# StepDrv.net
KiCad netlist of a schematic drawn in EAGLE
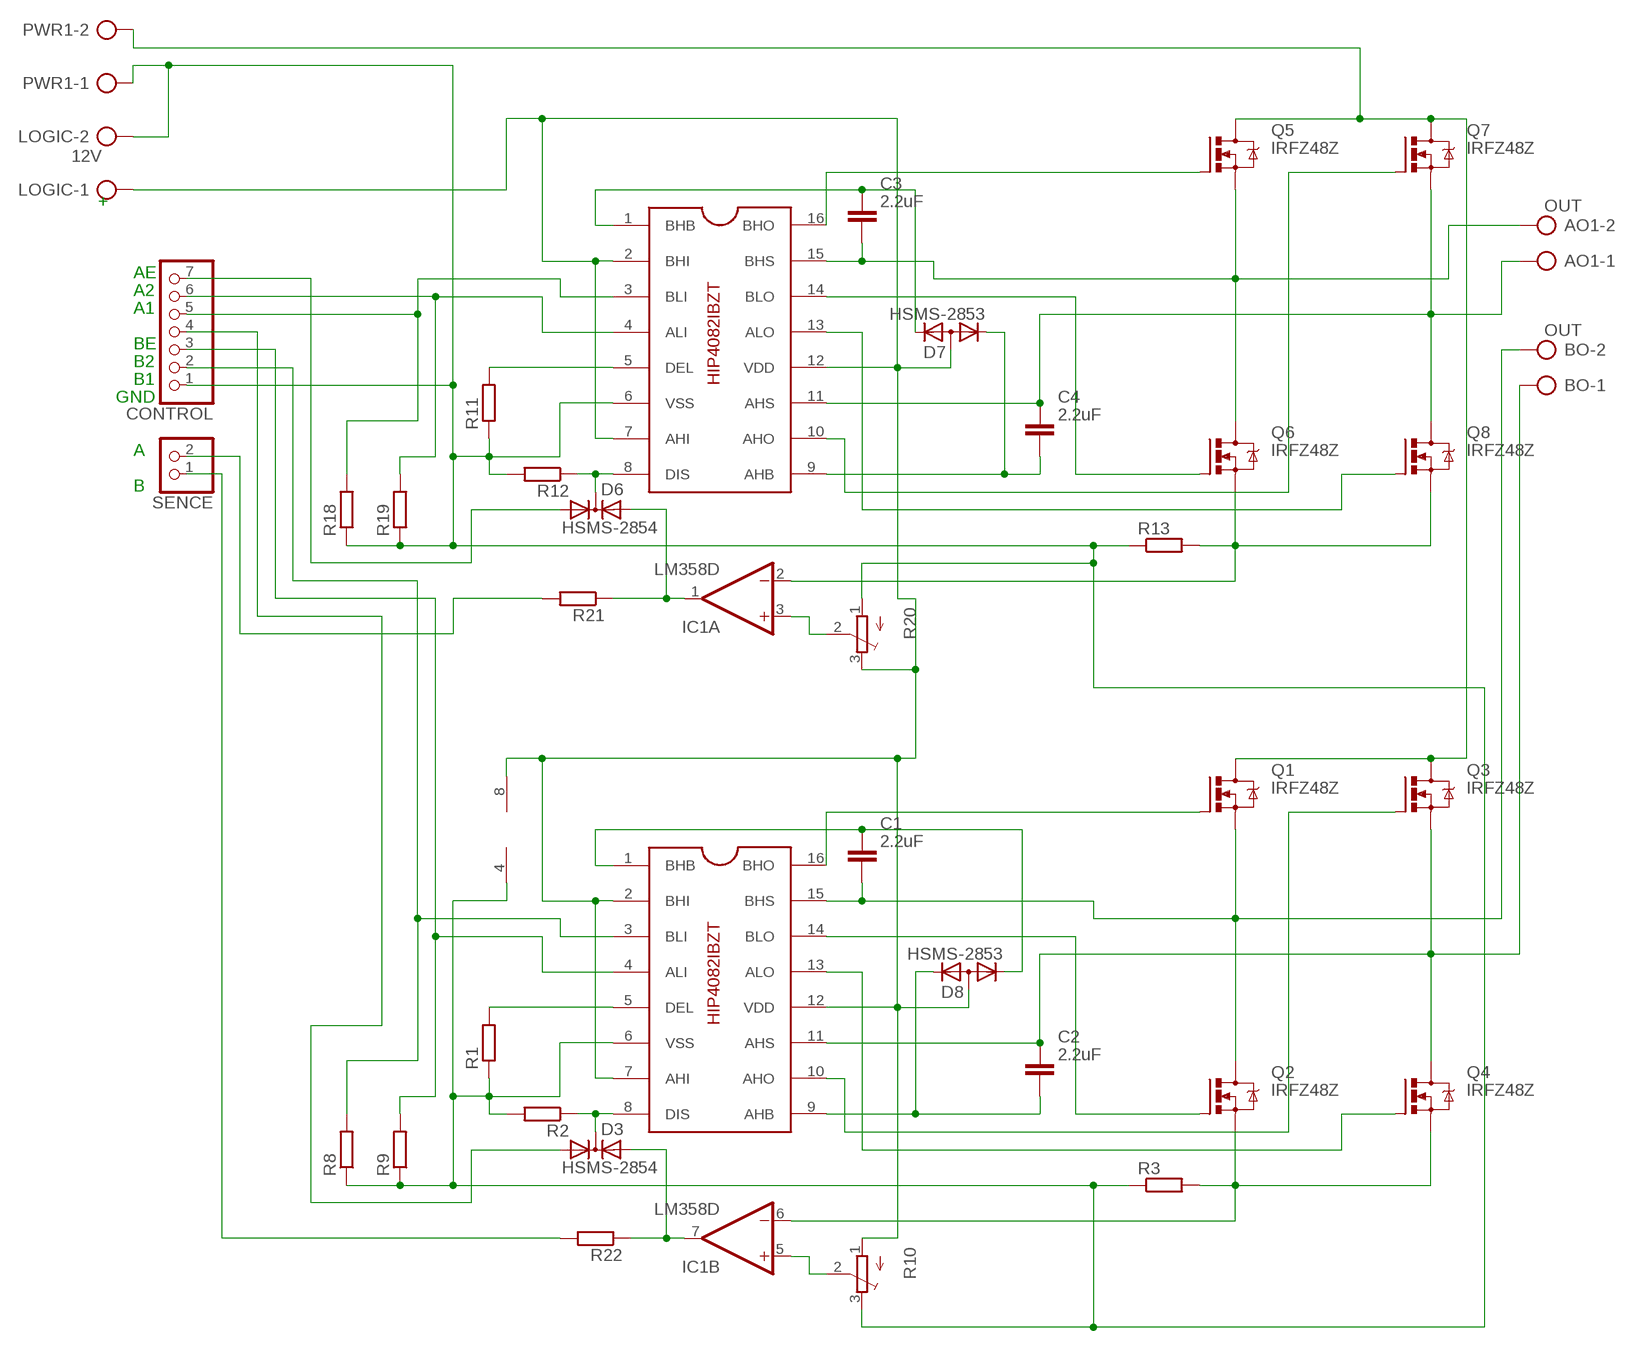
[diagram p0: schematic, sheet 1]

(export (version "E")
  (design (tool "Eeschema 10.0.6"))
  (components
    (comp (ref "AO1")
      (value "OUT")
      (footprint "eagle-import:AK300_2")
      (libsource (lib "eagle-import") (part "AK300/2"))
    )
    (comp (ref "BO")
      (value "OUT")
      (footprint "eagle-import:AK300_2")
      (libsource (lib "eagle-import") (part "AK300/2"))
    )
    (comp (ref "C1")
      (value "2.2uF")
      (footprint "eagle-import:C1206")
      (libsource (lib "eagle-import") (part "CAPACITOR_NPOL-1206"))
    )
    (comp (ref "C2")
      (value "2.2uF")
      (footprint "eagle-import:C1206")
      (libsource (lib "eagle-import") (part "CAPACITOR_NPOL-1206"))
    )
    (comp (ref "C3")
      (value "2.2uF")
      (footprint "eagle-import:C1206")
      (libsource (lib "eagle-import") (part "CAPACITOR_NPOL-1206"))
    )
    (comp (ref "C4")
      (value "2.2uF")
      (footprint "eagle-import:C1206")
      (libsource (lib "eagle-import") (part "CAPACITOR_NPOL-1206"))
    )
    (comp (ref "CONTROL")
      (value "PINHD-1X7")
      (footprint "eagle-import:1X07")
      (libsource (lib "eagle-import") (part "PINHD-1X7"))
    )
    (comp (ref "D3")
      (value "HSMS-2854")
      (footprint "eagle-import:SOT23")
      (libsource (lib "eagle-import") (part "HSMS-2854"))
    )
    (comp (ref "D6")
      (value "HSMS-2854")
      (footprint "eagle-import:SOT23")
      (libsource (lib "eagle-import") (part "HSMS-2854"))
    )
    (comp (ref "D7")
      (value "HSMS-2853")
      (footprint "eagle-import:SOT23")
      (libsource (lib "eagle-import") (part "HSMS-2853"))
    )
    (comp (ref "D8")
      (value "HSMS-2853")
      (footprint "eagle-import:SOT23")
      (libsource (lib "eagle-import") (part "HSMS-2853"))
    )
    (comp (ref "IC1")
      (value "LM358D")
      (footprint "eagle-import:SO08")
      (libsource (lib "eagle-import") (part "LM358D"))
    )
    (comp (ref "LOGIC")
      (value "12V")
      (footprint "eagle-import:AK300_2")
      (libsource (lib "eagle-import") (part "AK300/2"))
    )
    (comp (ref "PWR1")
      (value "AK300/2")
      (footprint "eagle-import:AK300_2")
      (libsource (lib "eagle-import") (part "AK300/2"))
    )
    (comp (ref "Q1")
      (value "IRFZ48Z")
      (footprint "eagle-import:TO220BH")
      (libsource (lib "eagle-import") (part "IRFZ48Z"))
    )
    (comp (ref "Q2")
      (value "IRFZ48Z")
      (footprint "eagle-import:TO220BH")
      (libsource (lib "eagle-import") (part "IRFZ48Z"))
    )
    (comp (ref "Q3")
      (value "IRFZ48Z")
      (footprint "eagle-import:TO220BH")
      (libsource (lib "eagle-import") (part "IRFZ48Z"))
    )
    (comp (ref "Q4")
      (value "IRFZ48Z")
      (footprint "eagle-import:TO220BH")
      (libsource (lib "eagle-import") (part "IRFZ48Z"))
    )
    (comp (ref "Q5")
      (value "IRFZ48Z")
      (footprint "eagle-import:TO220BH")
      (libsource (lib "eagle-import") (part "IRFZ48Z"))
    )
    (comp (ref "Q6")
      (value "IRFZ48Z")
      (footprint "eagle-import:TO220BH")
      (libsource (lib "eagle-import") (part "IRFZ48Z"))
    )
    (comp (ref "Q7")
      (value "IRFZ48Z")
      (footprint "eagle-import:TO220BH")
      (libsource (lib "eagle-import") (part "IRFZ48Z"))
    )
    (comp (ref "Q8")
      (value "IRFZ48Z")
      (footprint "eagle-import:TO220BH")
      (libsource (lib "eagle-import") (part "IRFZ48Z"))
    )
    (comp (ref "R1")
      (value "R-EU_R1206")
      (footprint "eagle-import:R1206")
      (libsource (lib "eagle-import") (part "R-EU_R1206"))
    )
    (comp (ref "R2")
      (value "R-EU_R1206")
      (footprint "eagle-import:R1206")
      (libsource (lib "eagle-import") (part "R-EU_R1206"))
    )
    (comp (ref "R3")
      (value "R-EU_0922/22")
      (footprint "eagle-import:0922_22")
      (libsource (lib "eagle-import") (part "R-EU_0922/22"))
    )
    (comp (ref "R8")
      (value "R-EU_M1206")
      (footprint "eagle-import:M1206")
      (libsource (lib "eagle-import") (part "R-EU_M1206"))
    )
    (comp (ref "R9")
      (value "R-EU_M1206")
      (footprint "eagle-import:M1206")
      (libsource (lib "eagle-import") (part "R-EU_M1206"))
    )
    (comp (ref "R10")
      (value "TRIM_EU-3223G")
      (footprint "eagle-import:3223G")
      (libsource (lib "eagle-import") (part "TRIM_EU-3223G"))
    )
    (comp (ref "R11")
      (value "R-EU_R1206")
      (footprint "eagle-import:R1206")
      (libsource (lib "eagle-import") (part "R-EU_R1206"))
    )
    (comp (ref "R12")
      (value "R-EU_R1206")
      (footprint "eagle-import:R1206")
      (libsource (lib "eagle-import") (part "R-EU_R1206"))
    )
    (comp (ref "R13")
      (value "R-EU_0922/22")
      (footprint "eagle-import:0922_22")
      (libsource (lib "eagle-import") (part "R-EU_0922/22"))
    )
    (comp (ref "R18")
      (value "R-EU_M1206")
      (footprint "eagle-import:M1206")
      (libsource (lib "eagle-import") (part "R-EU_M1206"))
    )
    (comp (ref "R19")
      (value "R-EU_M1206")
      (footprint "eagle-import:M1206")
      (libsource (lib "eagle-import") (part "R-EU_M1206"))
    )
    (comp (ref "R20")
      (value "TRIM_EU-3223G")
      (footprint "eagle-import:3223G")
      (libsource (lib "eagle-import") (part "TRIM_EU-3223G"))
    )
    (comp (ref "R21")
      (value "R-EU_M1206")
      (footprint "eagle-import:M1206")
      (libsource (lib "eagle-import") (part "R-EU_M1206"))
    )
    (comp (ref "R22")
      (value "R-EU_M1206")
      (footprint "eagle-import:M1206")
      (libsource (lib "eagle-import") (part "R-EU_M1206"))
    )
    (comp (ref "SENCE")
      (value "PINHD-1X2")
      (footprint "eagle-import:1X02")
      (libsource (lib "eagle-import") (part "PINHD-1X2"))
    )
    (comp (ref "U$1")
      (value "HIP4082IBZT")
      (footprint "eagle-import:SO16")
      (libsource (lib "eagle-import") (part "HIP4082IBZT"))
    )
    (comp (ref "U$2")
      (value "HIP4082IBZT")
      (footprint "eagle-import:SO16")
      (libsource (lib "eagle-import") (part "HIP4082IBZT"))
    )
  )
  (nets
    (net (code "1") (name "Net-(AO1A-KL)") (class "Default")
      (node (ref "AO1") (pin "1") (pinfunction "KL_1") (pintype "passive"))
      (node (ref "C4") (pin "1") (pinfunction "1_1") (pintype "passive"))
      (node (ref "Q7") (pin "S") (pinfunction "S_S") (pintype "passive"))
      (node (ref "Q8") (pin "D") (pinfunction "D_D") (pintype "passive"))
      (node (ref "U$2") (pin "11") (pinfunction "AHS_11") (pintype "output"))
    )
    (net (code "2") (name "Net-(AO1B-KL)") (class "Default")
      (node (ref "AO1") (pin "2") (pinfunction "KL_2") (pintype "passive"))
      (node (ref "C3") (pin "2") (pinfunction "2_2") (pintype "passive"))
      (node (ref "Q5") (pin "S") (pinfunction "S_S") (pintype "passive"))
      (node (ref "Q6") (pin "D") (pinfunction "D_D") (pintype "passive"))
      (node (ref "U$2") (pin "15") (pinfunction "BHS_15") (pintype "output"))
    )
    (net (code "3") (name "Net-(BOA-KL)") (class "Default")
      (node (ref "BO") (pin "1") (pinfunction "KL_1") (pintype "passive"))
      (node (ref "C2") (pin "1") (pinfunction "1_1") (pintype "passive"))
      (node (ref "Q3") (pin "S") (pinfunction "S_S") (pintype "passive"))
      (node (ref "Q4") (pin "D") (pinfunction "D_D") (pintype "passive"))
      (node (ref "U$1") (pin "11") (pinfunction "AHS_11") (pintype "output"))
    )
    (net (code "4") (name "Net-(BOB-KL)") (class "Default")
      (node (ref "BO") (pin "2") (pinfunction "KL_2") (pintype "passive"))
      (node (ref "C1") (pin "2") (pinfunction "2_2") (pintype "passive"))
      (node (ref "Q1") (pin "S") (pinfunction "S_S") (pintype "passive"))
      (node (ref "Q2") (pin "D") (pinfunction "D_D") (pintype "passive"))
      (node (ref "U$1") (pin "15") (pinfunction "BHS_15") (pintype "output"))
    )
    (net (code "5") (name "Net-(D3-A1)") (class "Default")
      (node (ref "CONTROL") (pin "4") (pinfunction "4_4") (pintype "passive"))
      (node (ref "D3") (pin "1") (pinfunction "A1_1") (pintype "passive"))
    )
    (net (code "6") (name "Net-(D3-A2)") (class "Default")
      (node (ref "D3") (pin "2") (pinfunction "A2_2") (pintype "passive"))
      (node (ref "IC1") (pin "7") (pinfunction "OUT_7") (pintype "output"))
      (node (ref "R22") (pin "1") (pinfunction "1_1") (pintype "passive"))
    )
    (net (code "7") (name "Net-(D3-C)") (class "Default")
      (node (ref "D3") (pin "3") (pinfunction "C_3") (pintype "passive"))
      (node (ref "R2") (pin "1") (pinfunction "1_1") (pintype "passive"))
      (node (ref "U$1") (pin "8") (pinfunction "DIS_8") (pintype "input"))
    )
    (net (code "8") (name "Net-(D6-A1)") (class "Default")
      (node (ref "CONTROL") (pin "7") (pinfunction "7_7") (pintype "passive"))
      (node (ref "D6") (pin "1") (pinfunction "A1_1") (pintype "passive"))
    )
    (net (code "9") (name "Net-(D6-A2)") (class "Default")
      (node (ref "D6") (pin "2") (pinfunction "A2_2") (pintype "passive"))
      (node (ref "IC1") (pin "1") (pinfunction "OUT_1") (pintype "output"))
      (node (ref "R21") (pin "1") (pinfunction "1_1") (pintype "passive"))
    )
    (net (code "10") (name "Net-(D6-C)") (class "Default")
      (node (ref "D6") (pin "3") (pinfunction "C_3") (pintype "passive"))
      (node (ref "R12") (pin "1") (pinfunction "1_1") (pintype "passive"))
      (node (ref "U$2") (pin "8") (pinfunction "DIS_8") (pintype "input"))
    )
    (net (code "11") (name "Net-(D7-A)") (class "Default")
      (node (ref "D7") (pin "3") (pinfunction "A_3") (pintype "passive"))
      (node (ref "D8") (pin "3") (pinfunction "A_3") (pintype "passive"))
      (node (ref "IC1") (pin "8") (pinfunction "V+_8") (pintype "power_in"))
      (node (ref "LOGIC") (pin "1") (pinfunction "KL_1") (pintype "passive"))
      (node (ref "R10") (pin "1") (pinfunction "A_1") (pintype "passive"))
      (node (ref "R20") (pin "3") (pinfunction "E_3") (pintype "passive"))
      (node (ref "U$1") (pin "12") (pinfunction "VDD_12") (pintype "power_in"))
      (node (ref "U$1") (pin "2") (pinfunction "BHI_2") (pintype "input"))
      (node (ref "U$1") (pin "7") (pinfunction "AHI_7") (pintype "input"))
      (node (ref "U$2") (pin "12") (pinfunction "VDD_12") (pintype "power_in"))
      (node (ref "U$2") (pin "2") (pinfunction "BHI_2") (pintype "input"))
      (node (ref "U$2") (pin "7") (pinfunction "AHI_7") (pintype "input"))
    )
    (net (code "12") (name "Net-(D7-K1)") (class "Default")
      (node (ref "C4") (pin "2") (pinfunction "2_2") (pintype "passive"))
      (node (ref "D7") (pin "1") (pinfunction "K1_1") (pintype "passive"))
      (node (ref "U$2") (pin "9") (pinfunction "AHB_9") (pintype "output"))
    )
    (net (code "13") (name "Net-(D7-K2)") (class "Default")
      (node (ref "C3") (pin "1") (pinfunction "1_1") (pintype "passive"))
      (node (ref "D7") (pin "2") (pinfunction "K2_2") (pintype "passive"))
      (node (ref "U$2") (pin "1") (pinfunction "BHB_1") (pintype "input"))
    )
    (net (code "14") (name "Net-(D8-K1)") (class "Default")
      (node (ref "C1") (pin "1") (pinfunction "1_1") (pintype "passive"))
      (node (ref "D8") (pin "1") (pinfunction "K1_1") (pintype "passive"))
      (node (ref "U$1") (pin "1") (pinfunction "BHB_1") (pintype "input"))
    )
    (net (code "15") (name "Net-(D8-K2)") (class "Default")
      (node (ref "C2") (pin "2") (pinfunction "2_2") (pintype "passive"))
      (node (ref "D8") (pin "2") (pinfunction "K2_2") (pintype "passive"))
      (node (ref "U$1") (pin "9") (pinfunction "AHB_9") (pintype "output"))
    )
    (net (code "16") (name "Net-(IC1A-+IN)") (class "Default")
      (node (ref "IC1") (pin "3") (pinfunction "+IN_3") (pintype "input"))
      (node (ref "R20") (pin "2") (pinfunction "S_2") (pintype "passive"))
    )
    (net (code "17") (name "Net-(IC1A--IN)") (class "Default")
      (node (ref "IC1") (pin "2") (pinfunction "-IN_2") (pintype "input"))
      (node (ref "Q6") (pin "S") (pinfunction "S_S") (pintype "passive"))
      (node (ref "Q8") (pin "S") (pinfunction "S_S") (pintype "passive"))
      (node (ref "R13") (pin "2") (pinfunction "2_2") (pintype "passive"))
    )
    (net (code "18") (name "Net-(IC1B-+IN)") (class "Default")
      (node (ref "IC1") (pin "5") (pinfunction "+IN_5") (pintype "input"))
      (node (ref "R10") (pin "2") (pinfunction "S_2") (pintype "passive"))
    )
    (net (code "19") (name "Net-(IC1B--IN)") (class "Default")
      (node (ref "IC1") (pin "6") (pinfunction "-IN_6") (pintype "input"))
      (node (ref "Q2") (pin "S") (pinfunction "S_S") (pintype "passive"))
      (node (ref "Q4") (pin "S") (pinfunction "S_S") (pintype "passive"))
      (node (ref "R3") (pin "2") (pinfunction "2_2") (pintype "passive"))
    )
    (net (code "20") (name "Net-(IC1C-V-)") (class "Default")
      (node (ref "CONTROL") (pin "1") (pinfunction "1_1") (pintype "passive"))
      (node (ref "IC1") (pin "4") (pinfunction "V-_4") (pintype "power_in"))
      (node (ref "LOGIC") (pin "2") (pinfunction "KL_2") (pintype "passive"))
      (node (ref "PWR1") (pin "1") (pinfunction "KL_1") (pintype "passive"))
      (node (ref "R1") (pin "1") (pinfunction "1_1") (pintype "passive"))
      (node (ref "R10") (pin "3") (pinfunction "E_3") (pintype "passive"))
      (node (ref "R11") (pin "1") (pinfunction "1_1") (pintype "passive"))
      (node (ref "R12") (pin "2") (pinfunction "2_2") (pintype "passive"))
      (node (ref "R13") (pin "1") (pinfunction "1_1") (pintype "passive"))
      (node (ref "R18") (pin "1") (pinfunction "1_1") (pintype "passive"))
      (node (ref "R19") (pin "1") (pinfunction "1_1") (pintype "passive"))
      (node (ref "R2") (pin "2") (pinfunction "2_2") (pintype "passive"))
      (node (ref "R20") (pin "1") (pinfunction "A_1") (pintype "passive"))
      (node (ref "R3") (pin "1") (pinfunction "1_1") (pintype "passive"))
      (node (ref "R8") (pin "1") (pinfunction "1_1") (pintype "passive"))
      (node (ref "R9") (pin "1") (pinfunction "1_1") (pintype "passive"))
      (node (ref "U$1") (pin "6") (pinfunction "VSS_6") (pintype "power_in"))
      (node (ref "U$2") (pin "6") (pinfunction "VSS_6") (pintype "power_in"))
    )
    (net (code "21") (name "Net-(PWR1B-KL)") (class "Default")
      (node (ref "PWR1") (pin "2") (pinfunction "KL_2") (pintype "passive"))
      (node (ref "Q1") (pin "D") (pinfunction "D_D") (pintype "passive"))
      (node (ref "Q3") (pin "D") (pinfunction "D_D") (pintype "passive"))
      (node (ref "Q5") (pin "D") (pinfunction "D_D") (pintype "passive"))
      (node (ref "Q7") (pin "D") (pinfunction "D_D") (pintype "passive"))
    )
    (net (code "22") (name "Net-(R21-Pad2)") (class "Default")
      (node (ref "R21") (pin "2") (pinfunction "2_2") (pintype "passive"))
      (node (ref "SENCE") (pin "2") (pinfunction "2_2") (pintype "passive"))
    )
    (net (code "23") (name "Net-(R22-Pad2)") (class "Default")
      (node (ref "R22") (pin "2") (pinfunction "2_2") (pintype "passive"))
      (node (ref "SENCE") (pin "1") (pinfunction "1_1") (pintype "passive"))
    )
    (net (code "24") (name "Net-(U$1-AHO)") (class "Default")
      (node (ref "Q3") (pin "G") (pinfunction "G_G") (pintype "passive"))
      (node (ref "U$1") (pin "10") (pinfunction "AHO_10") (pintype "output"))
    )
    (net (code "25") (name "Net-(U$1-ALI)") (class "Default")
      (node (ref "CONTROL") (pin "3") (pinfunction "3_3") (pintype "passive"))
      (node (ref "R9") (pin "2") (pinfunction "2_2") (pintype "passive"))
      (node (ref "U$1") (pin "4") (pinfunction "ALI_4") (pintype "input"))
    )
    (net (code "26") (name "Net-(U$1-ALO)") (class "Default")
      (node (ref "Q4") (pin "G") (pinfunction "G_G") (pintype "passive"))
      (node (ref "U$1") (pin "13") (pinfunction "ALO_13") (pintype "output"))
    )
    (net (code "27") (name "Net-(U$1-BHO)") (class "Default")
      (node (ref "Q1") (pin "G") (pinfunction "G_G") (pintype "passive"))
      (node (ref "U$1") (pin "16") (pinfunction "BHO_16") (pintype "output"))
    )
    (net (code "28") (name "Net-(U$1-BLI)") (class "Default")
      (node (ref "CONTROL") (pin "2") (pinfunction "2_2") (pintype "passive"))
      (node (ref "R8") (pin "2") (pinfunction "2_2") (pintype "passive"))
      (node (ref "U$1") (pin "3") (pinfunction "BLI_3") (pintype "input"))
    )
    (net (code "29") (name "Net-(U$1-BLO)") (class "Default")
      (node (ref "Q2") (pin "G") (pinfunction "G_G") (pintype "passive"))
      (node (ref "U$1") (pin "14") (pinfunction "BLO_14") (pintype "output"))
    )
    (net (code "30") (name "Net-(U$1-DEL)") (class "Default")
      (node (ref "R1") (pin "2") (pinfunction "2_2") (pintype "passive"))
      (node (ref "U$1") (pin "5") (pinfunction "DEL_5") (pintype "input"))
    )
    (net (code "31") (name "Net-(U$2-AHO)") (class "Default")
      (node (ref "Q7") (pin "G") (pinfunction "G_G") (pintype "passive"))
      (node (ref "U$2") (pin "10") (pinfunction "AHO_10") (pintype "output"))
    )
    (net (code "32") (name "Net-(U$2-ALI)") (class "Default")
      (node (ref "CONTROL") (pin "6") (pinfunction "6_6") (pintype "passive"))
      (node (ref "R19") (pin "2") (pinfunction "2_2") (pintype "passive"))
      (node (ref "U$2") (pin "4") (pinfunction "ALI_4") (pintype "input"))
    )
    (net (code "33") (name "Net-(U$2-ALO)") (class "Default")
      (node (ref "Q8") (pin "G") (pinfunction "G_G") (pintype "passive"))
      (node (ref "U$2") (pin "13") (pinfunction "ALO_13") (pintype "output"))
    )
    (net (code "34") (name "Net-(U$2-BHO)") (class "Default")
      (node (ref "Q5") (pin "G") (pinfunction "G_G") (pintype "passive"))
      (node (ref "U$2") (pin "16") (pinfunction "BHO_16") (pintype "output"))
    )
    (net (code "35") (name "Net-(U$2-BLI)") (class "Default")
      (node (ref "CONTROL") (pin "5") (pinfunction "5_5") (pintype "passive"))
      (node (ref "R18") (pin "2") (pinfunction "2_2") (pintype "passive"))
      (node (ref "U$2") (pin "3") (pinfunction "BLI_3") (pintype "input"))
    )
    (net (code "36") (name "Net-(U$2-BLO)") (class "Default")
      (node (ref "Q6") (pin "G") (pinfunction "G_G") (pintype "passive"))
      (node (ref "U$2") (pin "14") (pinfunction "BLO_14") (pintype "output"))
    )
    (net (code "37") (name "Net-(U$2-DEL)") (class "Default")
      (node (ref "R11") (pin "2") (pinfunction "2_2") (pintype "passive"))
      (node (ref "U$2") (pin "5") (pinfunction "DEL_5") (pintype "input"))
    )
  )
)
